# TopLevel.net
KiCad netlist of a schematic drawn in Altium Designer
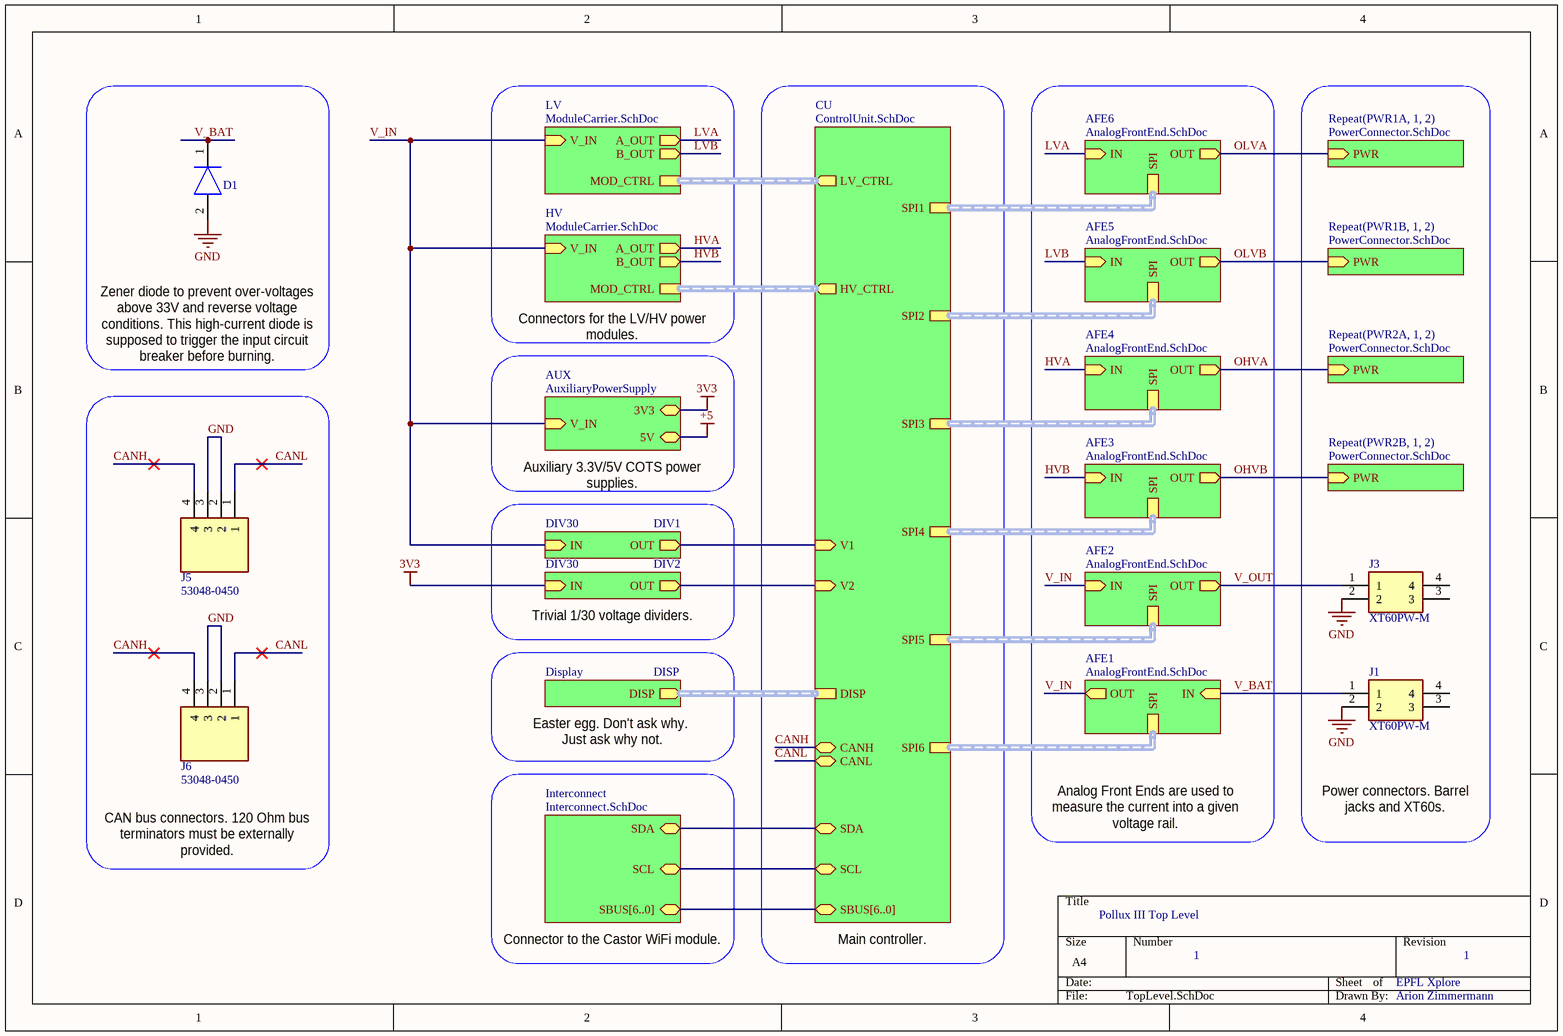
[diagram p0: TopLevel.SchDoc]

(export (version "E")
  (design (tool "Eeschema 10.0.6"))
  (components
    (comp (ref "D1")
      (value "BZG03C33-HM3-08")
      (footprint "SamacSys:DIOM5127X229N")
      (description "Diode")
      (fields (field (name "MOUSER PART NUMBER") "78-BZG03C33-HM3-08"))
      (libsource (lib "CarrierBoard") (part "BZG03C33-HM3-08"))
    )
    (comp (ref "J1")
      (value "XT60PW-M")
      (footprint "SamacSys:XT60PWM")
      (description "Connector")
      (libsource (lib "SamacSys") (part "XT60PW-M"))
    )
    (comp (ref "J3")
      (value "XT60PW-M")
      (footprint "SamacSys:XT60PWM")
      (description "Connector")
      (libsource (lib "SamacSys") (part "XT60PW-M"))
    )
    (comp (ref "J5")
      (value "53048-0450")
      (footprint "SHDRRA4W35P0X125_1X4_675X550X350P")
      (description "Connector")
      (fields (field (name "MOUSER PART NUMBER") "538-53048-0450"))
      (libsource (lib "*") (part "53048-0450"))
    )
    (comp (ref "J6")
      (value "53048-0450")
      (footprint "SHDRRA4W35P0X125_1X4_675X550X350P")
      (description "Connector")
      (fields (field (name "MOUSER PART NUMBER") "538-53048-0450"))
      (libsource (lib "*") (part "53048-0450"))
    )
  )
  (nets
    (net (code "3") (name "/CANH") (class "Default")
      (node (ref "J5") (pin "4") (pinfunction "4_4") (pintype "passive"))
      (node (ref "J6") (pin "4") (pinfunction "4_4") (pintype "passive"))
    )
    (net (code "4") (name "/CANL") (class "Default")
      (node (ref "J5") (pin "1") (pinfunction "1_1") (pintype "passive"))
      (node (ref "J6") (pin "1") (pinfunction "1_1") (pintype "passive"))
    )
    (net (code "27") (name "/V_BAT") (class "Default")
      (node (ref "D1") (pin "1") (pinfunction "K_1") (pintype "passive"))
      (node (ref "J1") (pin "1") (pinfunction "1_1") (pintype "passive"))
    )
    (net (code "29") (name "/V_OUT") (class "Default")
      (node (ref "J3") (pin "1") (pinfunction "1_1") (pintype "passive"))
    )
    (net (code "31") (name "GND") (class "Default")
      (node (ref "D1") (pin "2") (pinfunction "A_2") (pintype "passive"))
      (node (ref "J1") (pin "2") (pinfunction "2_2") (pintype "passive"))
      (node (ref "J3") (pin "2") (pinfunction "2_2") (pintype "passive"))
      (node (ref "J5") (pin "2") (pinfunction "2_2") (pintype "passive"))
      (node (ref "J5") (pin "3") (pinfunction "3_3") (pintype "passive"))
      (node (ref "J6") (pin "2") (pinfunction "2_2") (pintype "passive"))
      (node (ref "J6") (pin "3") (pinfunction "3_3") (pintype "passive"))
    )
    (net (code "32") (name "unconnected-(J1-Pad3)") (class "Default")
      (node (ref "J1") (pin "3") (pinfunction "3_3") (pintype "passive"))
    )
    (net (code "33") (name "unconnected-(J1-Pad4)") (class "Default")
      (node (ref "J1") (pin "4") (pinfunction "4_4") (pintype "passive"))
    )
    (net (code "34") (name "unconnected-(J3-Pad3)") (class "Default")
      (node (ref "J3") (pin "3") (pinfunction "3_3") (pintype "passive"))
    )
    (net (code "35") (name "unconnected-(J3-Pad4)") (class "Default")
      (node (ref "J3") (pin "4") (pinfunction "4_4") (pintype "passive"))
    )
  )
)
